# Integrador.net
KiCad netlist of a schematic drawn in EAGLE
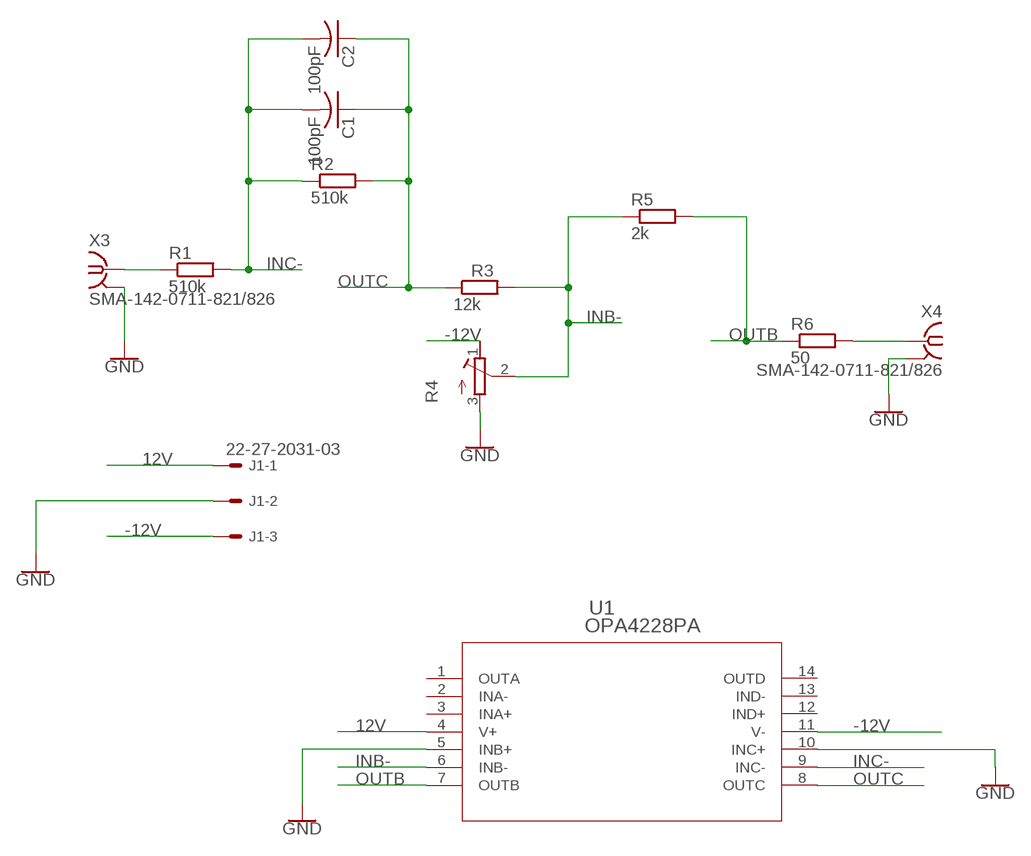
[diagram p0: schematic, sheet 1]

(export (version "E")
  (design (tool "Eeschema 10.0.6"))
  (components
    (comp (ref "C1")
      (value "100pF")
      (footprint "eagle-import:C025-030X050")
      (libsource (lib "eagle-import") (part "C-US025-030X050"))
    )
    (comp (ref "C2")
      (value "100pF")
      (footprint "eagle-import:C025-030X050")
      (libsource (lib "eagle-import") (part "C-US025-030X050"))
    )
    (comp (ref "J1")
      (value "22-27-2031-03")
      (footprint "eagle-import:6410-03")
      (fields (field (name "MF") "MOLEX"))
      (libsource (lib "eagle-import") (part "22-?-0327-2031"))
    )
    (comp (ref "R1")
      (value "510k")
      (footprint "eagle-import:0207_10")
      (libsource (lib "eagle-import") (part "R-EU_0207/10"))
    )
    (comp (ref "R2")
      (value "510k")
      (footprint "eagle-import:0207_10")
      (libsource (lib "eagle-import") (part "R-EU_0207/10"))
    )
    (comp (ref "R3")
      (value "12k")
      (footprint "eagle-import:0207_10")
      (libsource (lib "eagle-import") (part "R-EU_0207/10"))
    )
    (comp (ref "R4")
      (value "R-TRIMM3006P")
      (footprint "eagle-import:RTRIM3006P")
      (libsource (lib "eagle-import") (part "R-TRIMM3006P"))
    )
    (comp (ref "R5")
      (value "2k")
      (footprint "eagle-import:0207_10")
      (libsource (lib "eagle-import") (part "R-EU_0207/10"))
    )
    (comp (ref "R6")
      (value "50")
      (footprint "eagle-import:0207_10")
      (libsource (lib "eagle-import") (part "R-EU_0207/10"))
    )
    (comp (ref "U1")
      (value "OPA4228PA")
      (footprint "eagle-import:N14")
      (fields
        (field (name "GENERIC_PART_NUMBER") "OPA4228")
        (field (name "MANUFACTURER") "Texas Instruments")
      )
      (libsource (lib "eagle-import") (part "OPA4228PA"))
    )
    (comp (ref "X3")
      (value "SMA-142-0711-821/826")
      (footprint "eagle-import:J502-ND-142-0711-821_826")
      (fields (field (name "MF") "JOHNSON COMPONENTS") (field (name "MPN") "142-0711-821"))
      (libsource (lib "eagle-import") (part "SMA-142-0711-821/826"))
    )
    (comp (ref "X4")
      (value "SMA-142-0711-821/826")
      (footprint "eagle-import:J502-ND-142-0711-821_826")
      (fields (field (name "MF") "JOHNSON COMPONENTS") (field (name "MPN") "142-0711-821"))
      (libsource (lib "eagle-import") (part "SMA-142-0711-821/826"))
    )
  )
  (nets
    (net (code "1") (name "/-12V") (class "Default")
      (node (ref "J1") (pin "3") (pinfunction "S_3") (pintype "passive"))
      (node (ref "R4") (pin "1") (pinfunction "E_1") (pintype "passive"))
      (node (ref "U1") (pin "11") (pinfunction "V-_11") (pintype "power_in"))
    )
    (net (code "2") (name "/12V") (class "Default")
      (node (ref "J1") (pin "1") (pinfunction "S_1") (pintype "passive"))
      (node (ref "U1") (pin "4") (pinfunction "V+_4") (pintype "power_in"))
    )
    (net (code "3") (name "/INB-") (class "Default")
      (node (ref "R3") (pin "2") (pinfunction "2_2") (pintype "passive"))
      (node (ref "R4") (pin "2") (pinfunction "S_2") (pintype "passive"))
      (node (ref "R5") (pin "1") (pinfunction "1_1") (pintype "passive"))
      (node (ref "U1") (pin "6") (pinfunction "INB-_6") (pintype "input"))
    )
    (net (code "4") (name "/INC-") (class "Default")
      (node (ref "C1") (pin "2") (pinfunction "2_2") (pintype "passive"))
      (node (ref "C2") (pin "2") (pinfunction "2_2") (pintype "passive"))
      (node (ref "R1") (pin "2") (pinfunction "2_2") (pintype "passive"))
      (node (ref "R2") (pin "1") (pinfunction "1_1") (pintype "passive"))
      (node (ref "U1") (pin "9") (pinfunction "INC-_9") (pintype "input"))
    )
    (net (code "5") (name "/OUTB") (class "Default")
      (node (ref "R5") (pin "2") (pinfunction "2_2") (pintype "passive"))
      (node (ref "R6") (pin "1") (pinfunction "1_1") (pintype "passive"))
      (node (ref "U1") (pin "7") (pinfunction "OUTB_7") (pintype "output"))
    )
    (net (code "6") (name "/OUTC") (class "Default")
      (node (ref "C1") (pin "1") (pinfunction "1_1") (pintype "passive"))
      (node (ref "C2") (pin "1") (pinfunction "1_1") (pintype "passive"))
      (node (ref "R2") (pin "2") (pinfunction "2_2") (pintype "passive"))
      (node (ref "R3") (pin "1") (pinfunction "1_1") (pintype "passive"))
      (node (ref "U1") (pin "8") (pinfunction "OUTC_8") (pintype "output"))
    )
    (net (code "7") (name "GND") (class "Default")
      (node (ref "J1") (pin "2") (pinfunction "S_2") (pintype "passive"))
      (node (ref "R4") (pin "3") (pinfunction "A_3") (pintype "passive"))
      (node (ref "U1") (pin "10") (pinfunction "INC+_10") (pintype "input"))
      (node (ref "U1") (pin "5") (pinfunction "INB+_5") (pintype "input"))
      (node (ref "X3") (pin "G@1") (pinfunction "2_G@1") (pintype "passive"))
      (node (ref "X3") (pin "G@2") (pinfunction "2_G@2") (pintype "passive"))
      (node (ref "X3") (pin "G@3") (pinfunction "2_G@3") (pintype "passive"))
      (node (ref "X3") (pin "G@4") (pinfunction "2_G@4") (pintype "passive"))
      (node (ref "X4") (pin "G@1") (pinfunction "2_G@1") (pintype "passive"))
      (node (ref "X4") (pin "G@2") (pinfunction "2_G@2") (pintype "passive"))
      (node (ref "X4") (pin "G@3") (pinfunction "2_G@3") (pintype "passive"))
      (node (ref "X4") (pin "G@4") (pinfunction "2_G@4") (pintype "passive"))
    )
    (net (code "8") (name "Net-(R1-Pad1)") (class "Default")
      (node (ref "R1") (pin "1") (pinfunction "1_1") (pintype "passive"))
      (node (ref "X3") (pin "1") (pinfunction "1_1") (pintype "passive"))
    )
    (net (code "9") (name "Net-(R6-Pad2)") (class "Default")
      (node (ref "R6") (pin "2") (pinfunction "2_2") (pintype "passive"))
      (node (ref "X4") (pin "1") (pinfunction "1_1") (pintype "passive"))
    )
    (net (code "10") (name "unconnected-(U1-INA+-Pad3)") (class "Default")
      (node (ref "U1") (pin "3") (pinfunction "INA+_3") (pintype "input"))
    )
    (net (code "11") (name "unconnected-(U1-INA--Pad2)") (class "Default")
      (node (ref "U1") (pin "2") (pinfunction "INA-_2") (pintype "input"))
    )
    (net (code "12") (name "unconnected-(U1-IND+-Pad12)") (class "Default")
      (node (ref "U1") (pin "12") (pinfunction "IND+_12") (pintype "input"))
    )
    (net (code "13") (name "unconnected-(U1-IND--Pad13)") (class "Default")
      (node (ref "U1") (pin "13") (pinfunction "IND-_13") (pintype "input"))
    )
    (net (code "14") (name "unconnected-(U1-OUTA-Pad1)") (class "Default")
      (node (ref "U1") (pin "1") (pinfunction "OUTA_1") (pintype "output"))
    )
    (net (code "15") (name "unconnected-(U1-OUTD-Pad14)") (class "Default")
      (node (ref "U1") (pin "14") (pinfunction "OUTD_14") (pintype "output"))
    )
  )
)
